# LCD.net
KiCad netlist of a schematic drawn in Altium Designer
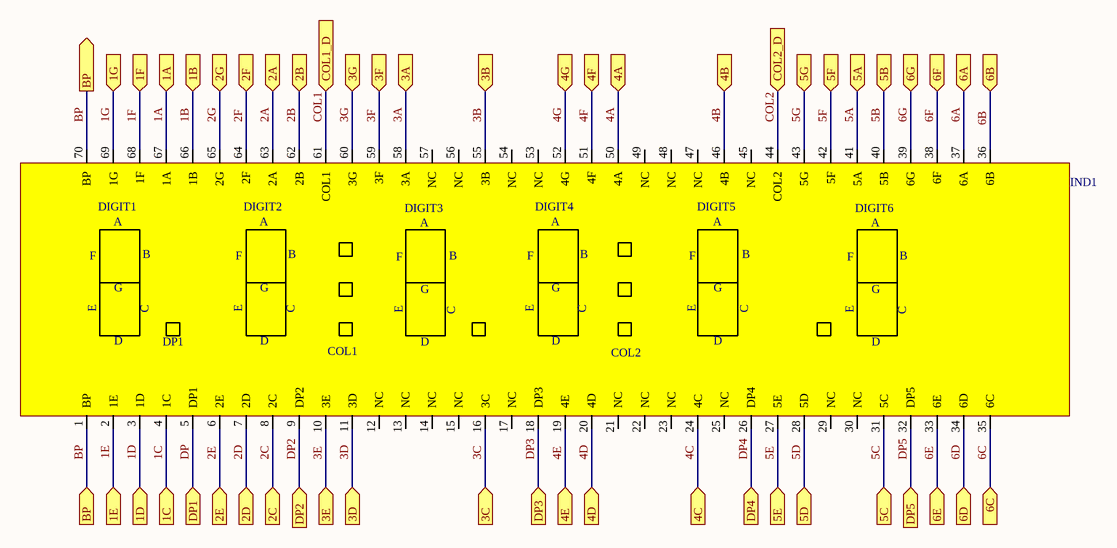
[diagram p0: LCD.SchDoc]

(export (version "E")
  (design (tool "Eeschema 10.0.6"))
  (components
    (comp (ref "IND1")
      (value "DE156")
      (footprint "IND_DE156")
      (description "6digit 7Segment indicator")
      (libsource (lib "gprs_modem_2") (part "IND7_DE156"))
    )
  )
  (nets
    (net (code "1") (name "/1A") (class "Default")
      (node (ref "IND1") (pin "67") (pinfunction "1A_67") (pintype "passive"))
    )
    (net (code "2") (name "/1B") (class "Default")
      (node (ref "IND1") (pin "66") (pinfunction "1B_66") (pintype "passive"))
    )
    (net (code "3") (name "/1C") (class "Default")
      (node (ref "IND1") (pin "4") (pinfunction "1C_4") (pintype "passive"))
    )
    (net (code "4") (name "/1D") (class "Default")
      (node (ref "IND1") (pin "3") (pinfunction "1D_3") (pintype "passive"))
    )
    (net (code "5") (name "/1E") (class "Default")
      (node (ref "IND1") (pin "2") (pinfunction "1E_2") (pintype "passive"))
    )
    (net (code "6") (name "/1F") (class "Default")
      (node (ref "IND1") (pin "68") (pinfunction "1F_68") (pintype "passive"))
    )
    (net (code "7") (name "/1G") (class "Default")
      (node (ref "IND1") (pin "69") (pinfunction "1G_69") (pintype "passive"))
    )
    (net (code "8") (name "/2A") (class "Default")
      (node (ref "IND1") (pin "63") (pinfunction "2A_63") (pintype "passive"))
    )
    (net (code "9") (name "/2B") (class "Default")
      (node (ref "IND1") (pin "62") (pinfunction "2B_62") (pintype "passive"))
    )
    (net (code "10") (name "/2C") (class "Default")
      (node (ref "IND1") (pin "8") (pinfunction "2C_8") (pintype "passive"))
    )
    (net (code "11") (name "/2D") (class "Default")
      (node (ref "IND1") (pin "7") (pinfunction "2D_7") (pintype "passive"))
    )
    (net (code "12") (name "/2E") (class "Default")
      (node (ref "IND1") (pin "6") (pinfunction "2E_6") (pintype "passive"))
    )
    (net (code "13") (name "/2F") (class "Default")
      (node (ref "IND1") (pin "64") (pinfunction "2F_64") (pintype "passive"))
    )
    (net (code "14") (name "/2G") (class "Default")
      (node (ref "IND1") (pin "65") (pinfunction "2G_65") (pintype "passive"))
    )
    (net (code "15") (name "/3A") (class "Default")
      (node (ref "IND1") (pin "58") (pinfunction "3A_58") (pintype "passive"))
    )
    (net (code "16") (name "/3B") (class "Default")
      (node (ref "IND1") (pin "55") (pinfunction "3B_55") (pintype "passive"))
    )
    (net (code "17") (name "/3C") (class "Default")
      (node (ref "IND1") (pin "16") (pinfunction "3C_16") (pintype "passive"))
    )
    (net (code "18") (name "/3D") (class "Default")
      (node (ref "IND1") (pin "11") (pinfunction "3D_11") (pintype "passive"))
    )
    (net (code "19") (name "/3E") (class "Default")
      (node (ref "IND1") (pin "10") (pinfunction "3E_10") (pintype "passive"))
    )
    (net (code "20") (name "/3F") (class "Default")
      (node (ref "IND1") (pin "59") (pinfunction "3F_59") (pintype "passive"))
    )
    (net (code "21") (name "/3G") (class "Default")
      (node (ref "IND1") (pin "60") (pinfunction "3G_60") (pintype "passive"))
    )
    (net (code "22") (name "/4A") (class "Default")
      (node (ref "IND1") (pin "50") (pinfunction "4A_50") (pintype "passive"))
    )
    (net (code "23") (name "/4B") (class "Default")
      (node (ref "IND1") (pin "46") (pinfunction "4B_46") (pintype "passive"))
    )
    (net (code "24") (name "/4C") (class "Default")
      (node (ref "IND1") (pin "24") (pinfunction "4C_24") (pintype "passive"))
    )
    (net (code "25") (name "/4D") (class "Default")
      (node (ref "IND1") (pin "20") (pinfunction "4D_20") (pintype "passive"))
    )
    (net (code "26") (name "/4E") (class "Default")
      (node (ref "IND1") (pin "19") (pinfunction "4E_19") (pintype "passive"))
    )
    (net (code "27") (name "/4F") (class "Default")
      (node (ref "IND1") (pin "51") (pinfunction "4F_51") (pintype "passive"))
    )
    (net (code "28") (name "/4G") (class "Default")
      (node (ref "IND1") (pin "52") (pinfunction "4G_52") (pintype "passive"))
    )
    (net (code "29") (name "/5A") (class "Default")
      (node (ref "IND1") (pin "41") (pinfunction "5A_41") (pintype "passive"))
    )
    (net (code "30") (name "/5B") (class "Default")
      (node (ref "IND1") (pin "40") (pinfunction "5B_40") (pintype "passive"))
    )
    (net (code "31") (name "/5C") (class "Default")
      (node (ref "IND1") (pin "31") (pinfunction "5C_31") (pintype "passive"))
    )
    (net (code "32") (name "/5D") (class "Default")
      (node (ref "IND1") (pin "28") (pinfunction "5D_28") (pintype "passive"))
    )
    (net (code "33") (name "/5E") (class "Default")
      (node (ref "IND1") (pin "27") (pinfunction "5E_27") (pintype "passive"))
    )
    (net (code "34") (name "/5F") (class "Default")
      (node (ref "IND1") (pin "42") (pinfunction "5F_42") (pintype "passive"))
    )
    (net (code "35") (name "/5G") (class "Default")
      (node (ref "IND1") (pin "43") (pinfunction "5G_43") (pintype "passive"))
    )
    (net (code "36") (name "/6A") (class "Default")
      (node (ref "IND1") (pin "37") (pinfunction "6A_37") (pintype "passive"))
    )
    (net (code "37") (name "/6B") (class "Default")
      (node (ref "IND1") (pin "36") (pinfunction "6B_36") (pintype "passive"))
    )
    (net (code "38") (name "/6C") (class "Default")
      (node (ref "IND1") (pin "35") (pinfunction "6C_35") (pintype "passive"))
    )
    (net (code "39") (name "/6D") (class "Default")
      (node (ref "IND1") (pin "34") (pinfunction "6D_34") (pintype "passive"))
    )
    (net (code "40") (name "/6E") (class "Default")
      (node (ref "IND1") (pin "33") (pinfunction "6E_33") (pintype "passive"))
    )
    (net (code "41") (name "/6F") (class "Default")
      (node (ref "IND1") (pin "38") (pinfunction "6F_38") (pintype "passive"))
    )
    (net (code "42") (name "/6G") (class "Default")
      (node (ref "IND1") (pin "39") (pinfunction "6G_39") (pintype "passive"))
    )
    (net (code "43") (name "/BP") (class "Default")
      (node (ref "IND1") (pin "1") (pinfunction "BP_1") (pintype "passive"))
      (node (ref "IND1") (pin "70") (pinfunction "BP_70") (pintype "passive"))
    )
    (net (code "44") (name "/COL1") (class "Default")
      (node (ref "IND1") (pin "61") (pinfunction "COL1_61") (pintype "passive"))
    )
    (net (code "45") (name "/COL2") (class "Default")
      (node (ref "IND1") (pin "44") (pinfunction "COL2_44") (pintype "passive"))
    )
    (net (code "46") (name "/DP") (class "Default")
      (node (ref "IND1") (pin "5") (pinfunction "DP1_5") (pintype "passive"))
    )
    (net (code "47") (name "/DP2") (class "Default")
      (node (ref "IND1") (pin "9") (pinfunction "DP2_9") (pintype "passive"))
    )
    (net (code "48") (name "/DP3") (class "Default")
      (node (ref "IND1") (pin "18") (pinfunction "DP3_18") (pintype "passive"))
    )
    (net (code "49") (name "/DP4") (class "Default")
      (node (ref "IND1") (pin "26") (pinfunction "DP4_26") (pintype "passive"))
    )
    (net (code "50") (name "/DP5") (class "Default")
      (node (ref "IND1") (pin "32") (pinfunction "DP5_32") (pintype "passive"))
    )
    (net (code "51") (name "unconnected-(IND1-NC-Pad12)") (class "Default")
      (node (ref "IND1") (pin "12") (pinfunction "NC_12") (pintype "passive"))
    )
    (net (code "52") (name "unconnected-(IND1-NC-Pad13)") (class "Default")
      (node (ref "IND1") (pin "13") (pinfunction "NC_13") (pintype "passive"))
    )
    (net (code "53") (name "unconnected-(IND1-NC-Pad14)") (class "Default")
      (node (ref "IND1") (pin "14") (pinfunction "NC_14") (pintype "passive"))
    )
    (net (code "54") (name "unconnected-(IND1-NC-Pad15)") (class "Default")
      (node (ref "IND1") (pin "15") (pinfunction "NC_15") (pintype "passive"))
    )
    (net (code "55") (name "unconnected-(IND1-NC-Pad17)") (class "Default")
      (node (ref "IND1") (pin "17") (pinfunction "NC_17") (pintype "passive"))
    )
    (net (code "56") (name "unconnected-(IND1-NC-Pad21)") (class "Default")
      (node (ref "IND1") (pin "21") (pinfunction "NC_21") (pintype "passive"))
    )
    (net (code "57") (name "unconnected-(IND1-NC-Pad22)") (class "Default")
      (node (ref "IND1") (pin "22") (pinfunction "NC_22") (pintype "passive"))
    )
    (net (code "58") (name "unconnected-(IND1-NC-Pad23)") (class "Default")
      (node (ref "IND1") (pin "23") (pinfunction "NC_23") (pintype "passive"))
    )
    (net (code "59") (name "unconnected-(IND1-NC-Pad25)") (class "Default")
      (node (ref "IND1") (pin "25") (pinfunction "NC_25") (pintype "passive"))
    )
    (net (code "60") (name "unconnected-(IND1-NC-Pad29)") (class "Default")
      (node (ref "IND1") (pin "29") (pinfunction "NC_29") (pintype "passive"))
    )
    (net (code "61") (name "unconnected-(IND1-NC-Pad30)") (class "Default")
      (node (ref "IND1") (pin "30") (pinfunction "NC_30") (pintype "passive"))
    )
    (net (code "62") (name "unconnected-(IND1-NC-Pad45)") (class "Default")
      (node (ref "IND1") (pin "45") (pinfunction "NC_45") (pintype "passive"))
    )
    (net (code "63") (name "unconnected-(IND1-NC-Pad47)") (class "Default")
      (node (ref "IND1") (pin "47") (pinfunction "NC_47") (pintype "passive"))
    )
    (net (code "64") (name "unconnected-(IND1-NC-Pad48)") (class "Default")
      (node (ref "IND1") (pin "48") (pinfunction "NC_48") (pintype "passive"))
    )
    (net (code "65") (name "unconnected-(IND1-NC-Pad49)") (class "Default")
      (node (ref "IND1") (pin "49") (pinfunction "NC_49") (pintype "passive"))
    )
    (net (code "66") (name "unconnected-(IND1-NC-Pad53)") (class "Default")
      (node (ref "IND1") (pin "53") (pinfunction "NC_53") (pintype "passive"))
    )
    (net (code "67") (name "unconnected-(IND1-NC-Pad54)") (class "Default")
      (node (ref "IND1") (pin "54") (pinfunction "NC_54") (pintype "passive"))
    )
    (net (code "68") (name "unconnected-(IND1-NC-Pad56)") (class "Default")
      (node (ref "IND1") (pin "56") (pinfunction "NC_56") (pintype "passive"))
    )
    (net (code "69") (name "unconnected-(IND1-NC-Pad57)") (class "Default")
      (node (ref "IND1") (pin "57") (pinfunction "NC_57") (pintype "passive"))
    )
  )
)
